# SCH_5G23-dev1_2022-10-18.net
KiCad netlist of a schematic drawn in EasyEDA
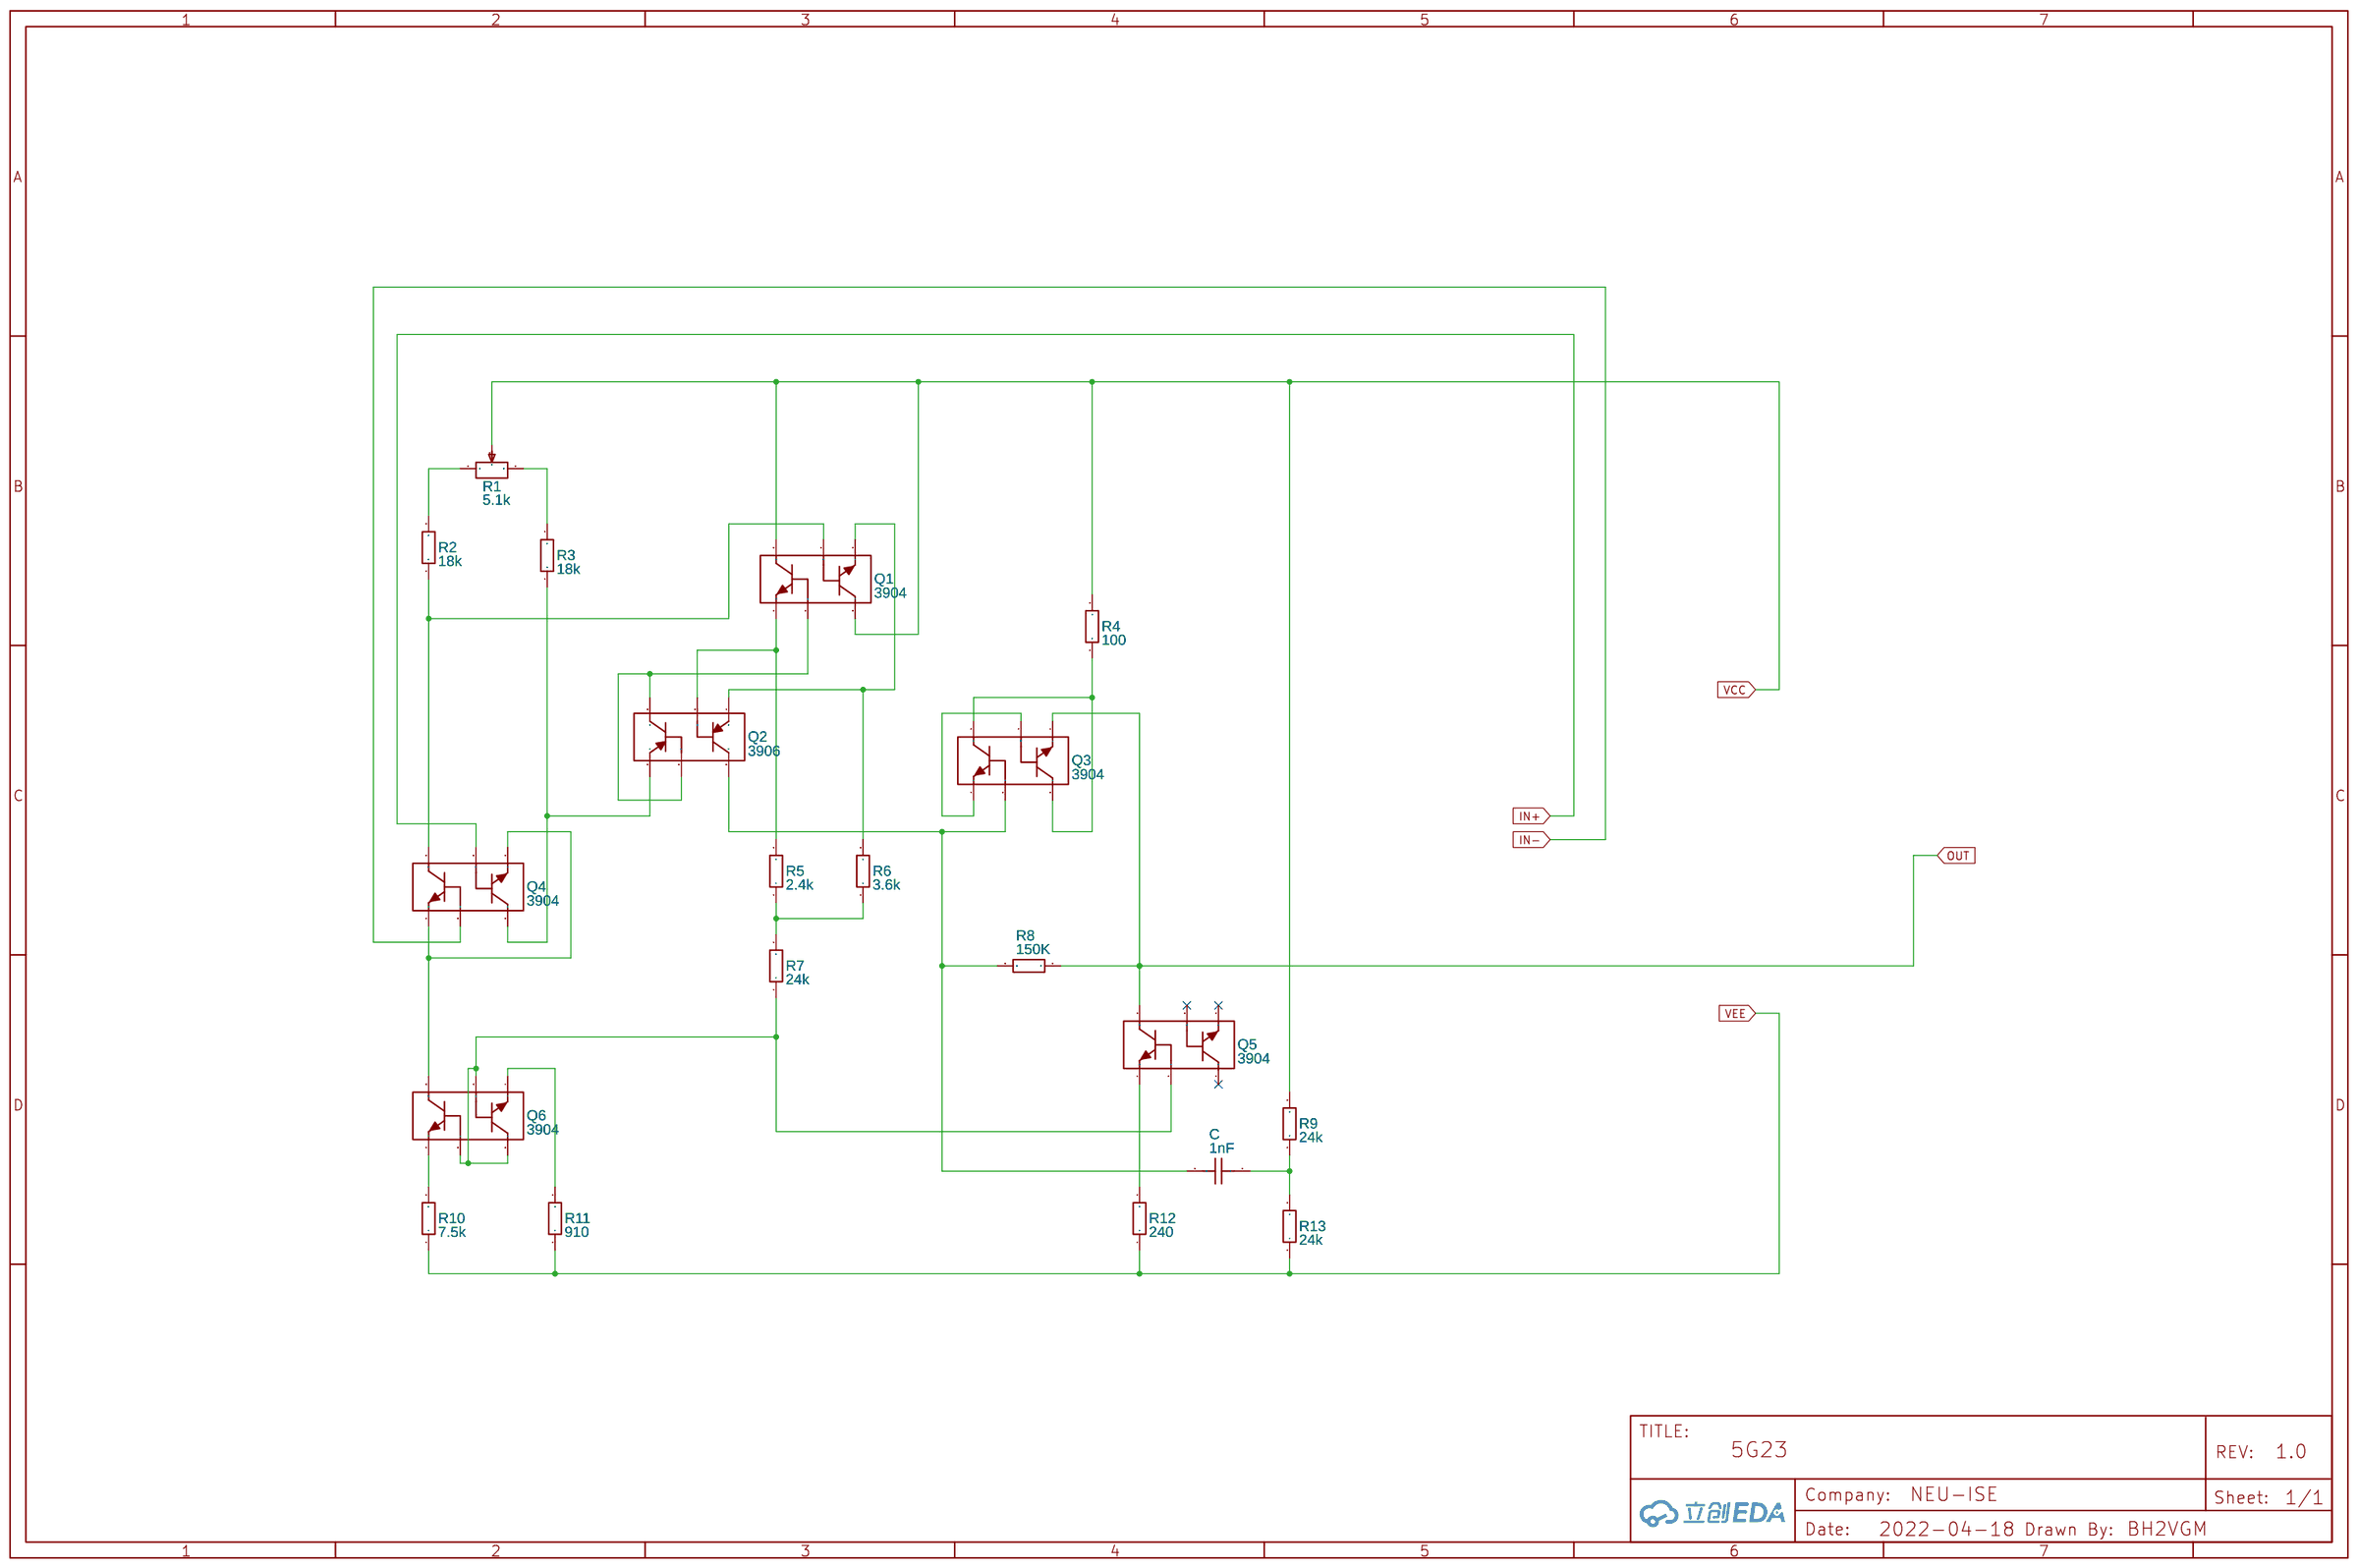
[diagram p0: 5G23]
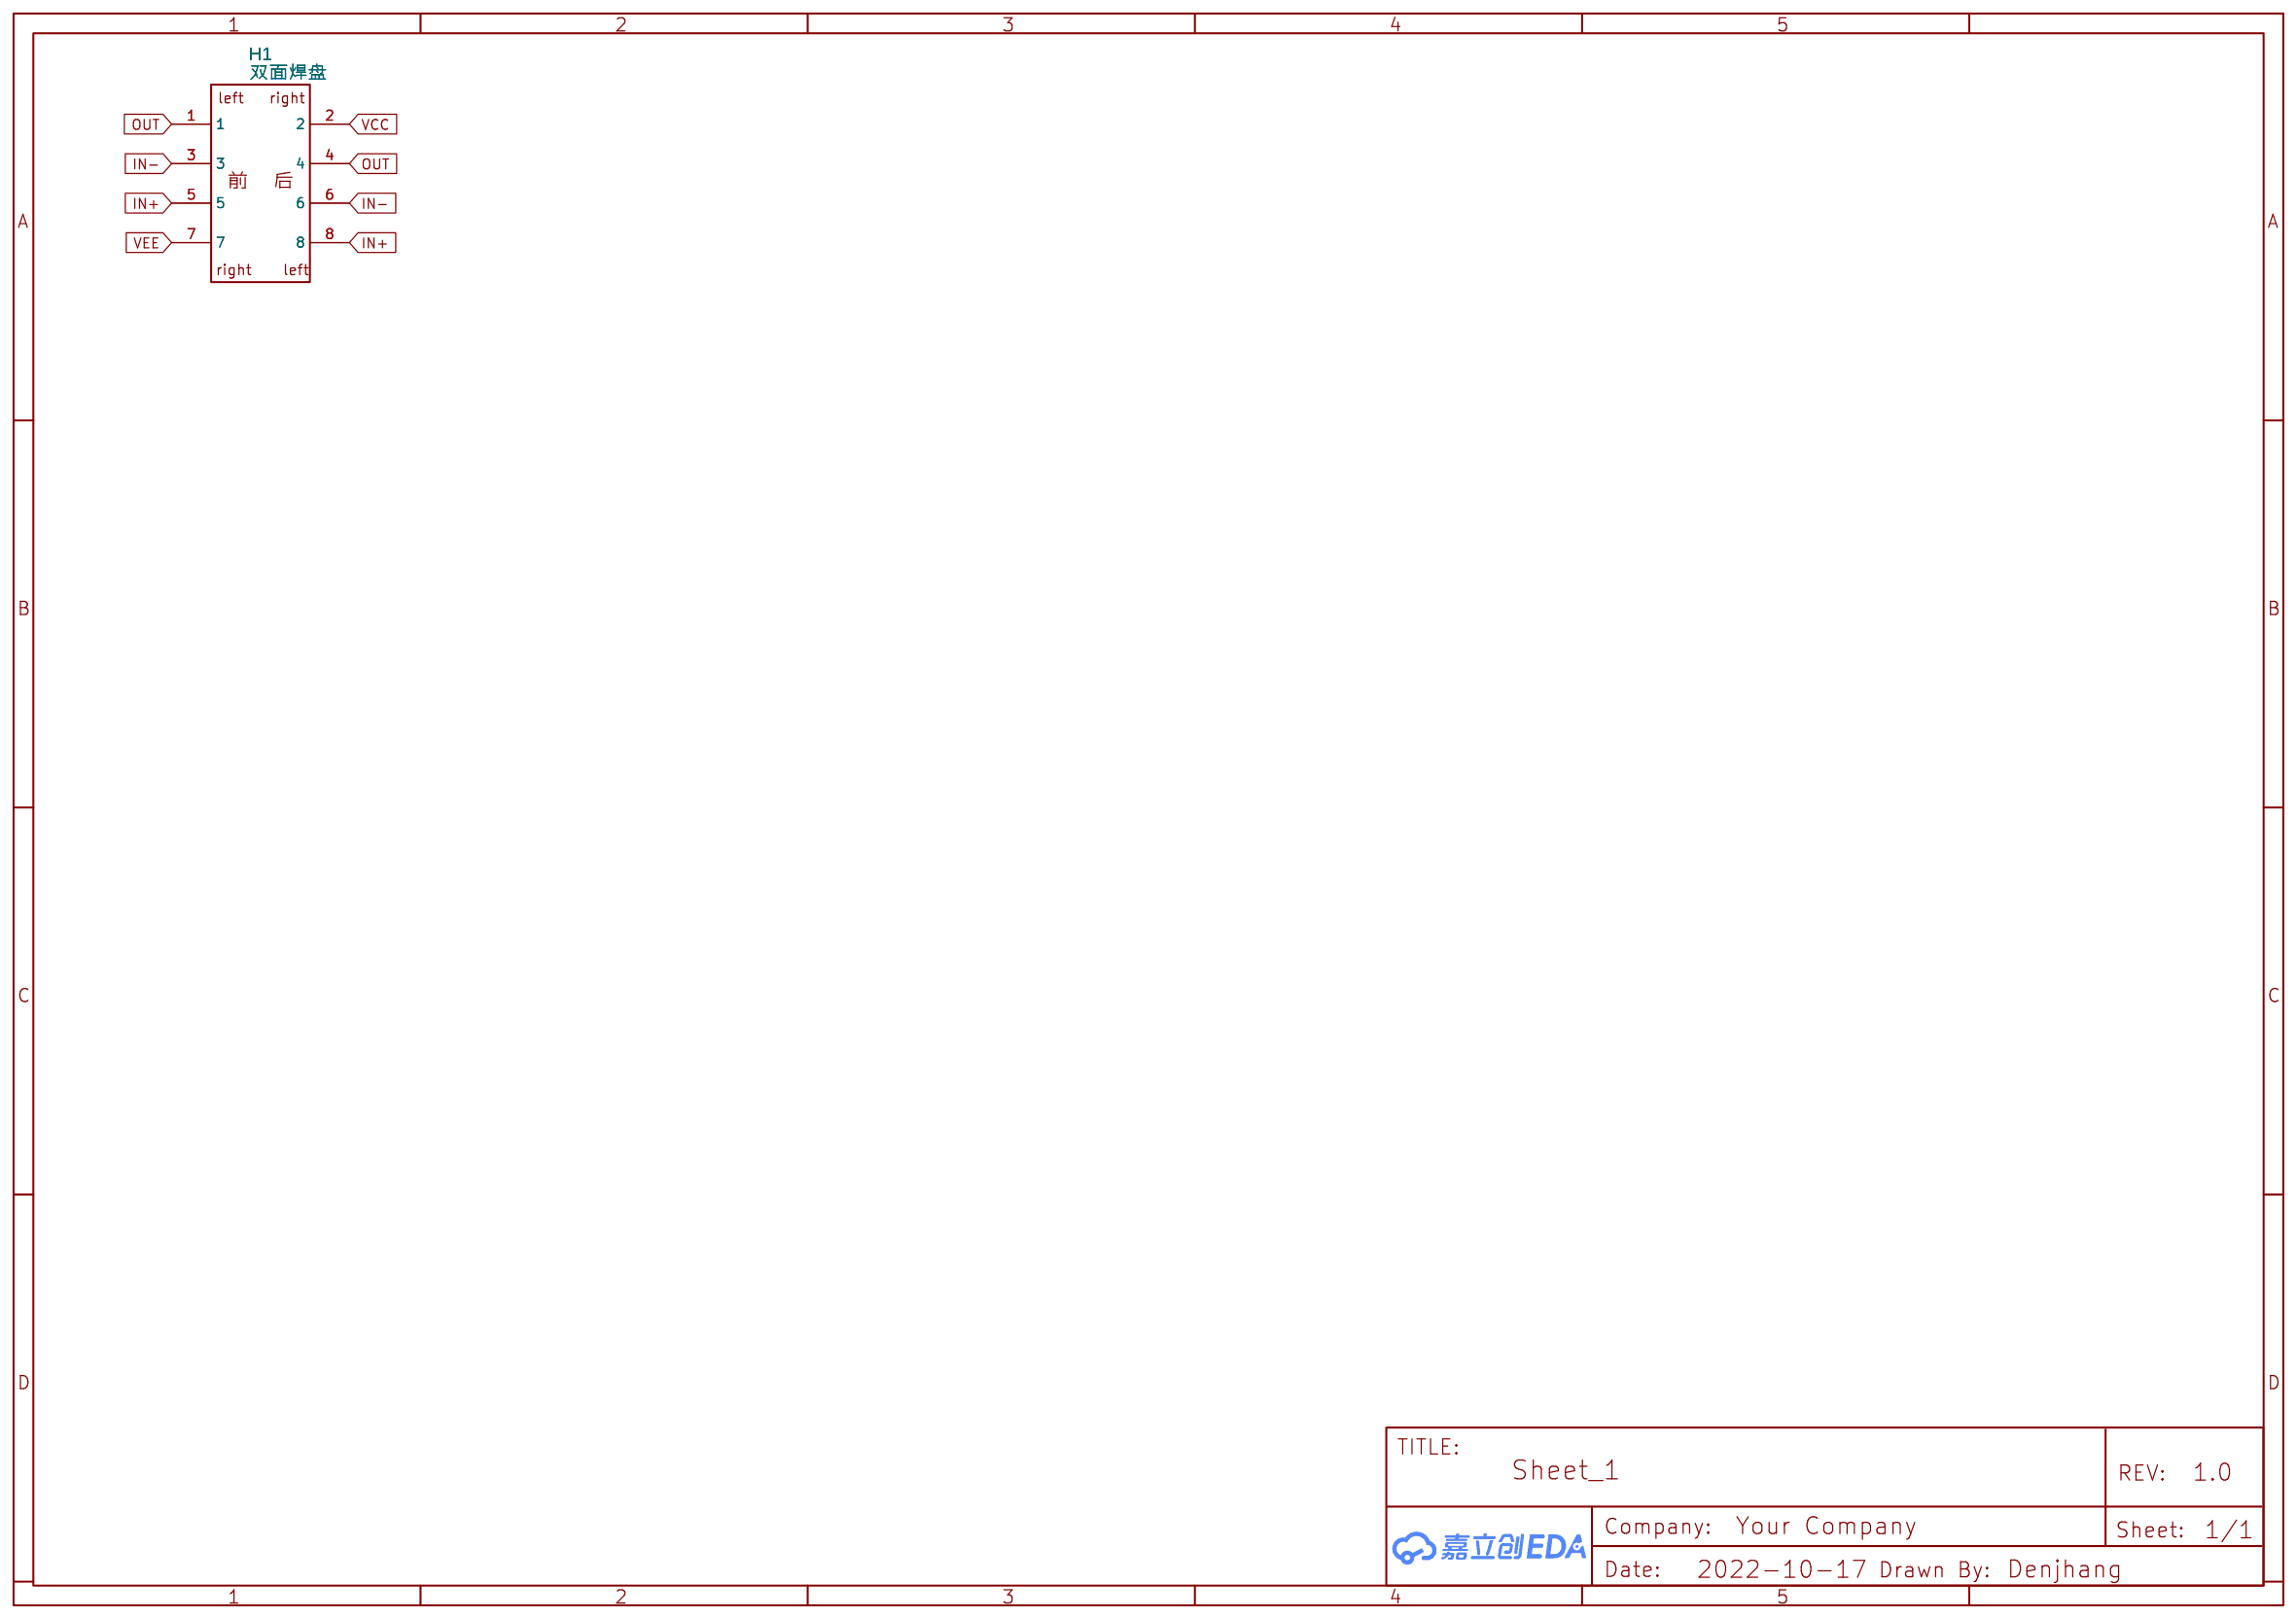
[diagram p1: CONN]

(export (version "E")
  (design (tool "Eeschema 10.0.6"))
  (components
    (comp (ref "C")
      (value "1nF")
      (fields
        (field (name "BOM_Manufacturer Part") "1nF-C0603")
        (field (name "BOM_Supplier Part") "C2940049")
      )
      (libsource (lib "") (part "1NF-C0603"))
    )
    (comp (ref "Q1")
      (value "3904")
      (fields
        (field (name "BOM_Manufacturer Part") "MMDT3904-7-F")
        (field (name "BOM_Supplier Part") "C83572")
      )
      (libsource (lib "") (part "MMDT3904"))
    )
    (comp (ref "Q2")
      (value "3906")
      (fields
        (field (name "BOM_Manufacturer Part") "MMDT3906-TP")
        (field (name "BOM_Supplier Part") "C779248")
      )
      (libsource (lib "") (part "MMDT3906"))
    )
    (comp (ref "Q3")
      (value "3904")
      (fields
        (field (name "BOM_Manufacturer Part") "MMDT3904-7-F")
        (field (name "BOM_Supplier Part") "C83572")
      )
      (libsource (lib "") (part "MMDT3904"))
    )
    (comp (ref "Q4")
      (value "3904")
      (fields
        (field (name "BOM_Manufacturer Part") "MMDT3904-7-F")
        (field (name "BOM_Supplier Part") "C83572")
      )
      (libsource (lib "") (part "MMDT3904"))
    )
    (comp (ref "Q5")
      (value "3904")
      (fields
        (field (name "BOM_Manufacturer Part") "MMDT3904-7-F")
        (field (name "BOM_Supplier Part") "C83572")
      )
      (libsource (lib "") (part "MMDT3904"))
    )
    (comp (ref "Q6")
      (value "3904")
      (fields
        (field (name "BOM_Manufacturer Part") "MMDT3904-7-F")
        (field (name "BOM_Supplier Part") "C83572")
      )
      (libsource (lib "") (part "MMDT3904"))
    )
    (comp (ref "R1")
      (value "5.1k")
      (fields
        (field (name "BOM_Manufacturer Part") "VG039NCHXTB204")
        (field (name "BOM_Supplier Part") "C128551")
      )
      (libsource (lib "") (part "VG039NCHXTB204"))
    )
    (comp (ref "R2")
      (value "18k")
      (fields (field (name "BOM_Manufacturer Part") "0805") (field (name "BOM_Supplier Part") "C9900012715"))
      (libsource (lib "") (part "0805_1"))
    )
    (comp (ref "R3")
      (value "18k")
      (fields (field (name "BOM_Manufacturer Part") "0805") (field (name "BOM_Supplier Part") "C9900012715"))
      (libsource (lib "") (part "0805_1"))
    )
    (comp (ref "R4")
      (value "100")
      (fields (field (name "BOM_Manufacturer Part") "0805") (field (name "BOM_Supplier Part") "C9900012715"))
      (libsource (lib "") (part "0805_1"))
    )
    (comp (ref "R5")
      (value "2.4k")
      (fields (field (name "BOM_Manufacturer Part") "0805") (field (name "BOM_Supplier Part") "C9900012715"))
      (libsource (lib "") (part "0805_1"))
    )
    (comp (ref "R6")
      (value "3.6k")
      (fields (field (name "BOM_Manufacturer Part") "0805") (field (name "BOM_Supplier Part") "C9900012715"))
      (libsource (lib "") (part "0805_1"))
    )
    (comp (ref "R7")
      (value "24k")
      (fields (field (name "BOM_Manufacturer Part") "0805") (field (name "BOM_Supplier Part") "C9900012715"))
      (libsource (lib "") (part "0805_1"))
    )
    (comp (ref "R8")
      (value "150K")
      (fields (field (name "BOM_Manufacturer Part") "0805") (field (name "BOM_Supplier Part") "C9900012715"))
      (libsource (lib "") (part "0805"))
    )
    (comp (ref "R9")
      (value "24k")
      (fields (field (name "BOM_Manufacturer Part") "0805") (field (name "BOM_Supplier Part") "C9900012715"))
      (libsource (lib "") (part "0805_1"))
    )
    (comp (ref "R10")
      (value "7.5k")
      (fields (field (name "BOM_Manufacturer Part") "0805") (field (name "BOM_Supplier Part") "C9900012715"))
      (libsource (lib "") (part "0805_1"))
    )
    (comp (ref "R11")
      (value "910")
      (fields (field (name "BOM_Manufacturer Part") "0805") (field (name "BOM_Supplier Part") "C9900012715"))
      (libsource (lib "") (part "0805_1"))
    )
    (comp (ref "R12")
      (value "240")
      (fields (field (name "BOM_Manufacturer Part") "0805") (field (name "BOM_Supplier Part") "C9900012715"))
      (libsource (lib "") (part "0805_1"))
    )
    (comp (ref "R13")
      (value "24k")
      (fields (field (name "BOM_Manufacturer Part") "0805") (field (name "BOM_Supplier Part") "C9900012715"))
      (libsource (lib "") (part "0805_1"))
    )
    (comp (ref "H1") (value "双面焊盘") (libsource (lib "") (part "双面焊盘")))
  )
  (nets
    (net (code "1") (name "IN+") (class "Default")
      (node (ref "H1") (pin "5") (pinfunction "5_5") (pintype "unspecified"))
      (node (ref "H1") (pin "8") (pinfunction "8_8") (pintype "unspecified"))
      (node (ref "Q4") (pin "5") (pinfunction "B_5") (pintype "unspecified"))
    )
    (net (code "2") (name "IN-") (class "Default")
      (node (ref "H1") (pin "3") (pinfunction "3_3") (pintype "unspecified"))
      (node (ref "H1") (pin "6") (pinfunction "6_6") (pintype "unspecified"))
      (node (ref "Q4") (pin "2") (pinfunction "B_2") (pintype "unspecified"))
    )
    (net (code "3") (name "Net-(C-Pad1)") (class "Default")
      (node (ref "C") (pin "1") (pinfunction "1_1") (pintype "unspecified"))
      (node (ref "Q2") (pin "3") (pinfunction "C_3") (pintype "unspecified"))
      (node (ref "Q3") (pin "2") (pinfunction "B_2") (pintype "unspecified"))
      (node (ref "R8") (pin "2") (pinfunction "2_2") (pintype "unspecified"))
    )
    (net (code "4") (name "Net-(C-Pad2)") (class "Default")
      (node (ref "C") (pin "2") (pinfunction "2_2") (pintype "unspecified"))
      (node (ref "R13") (pin "2") (pinfunction "2_2") (pintype "unspecified"))
      (node (ref "R9") (pin "1") (pinfunction "1_1") (pintype "unspecified"))
    )
    (net (code "5") (name "Net-(Q1-B-Pad2)") (class "Default")
      (node (ref "Q1") (pin "2") (pinfunction "B_2") (pintype "unspecified"))
      (node (ref "Q2") (pin "2") (pinfunction "B_2") (pintype "unspecified"))
      (node (ref "Q2") (pin "6") (pinfunction "C_6") (pintype "unspecified"))
    )
    (net (code "6") (name "Net-(Q1-B-Pad5)") (class "Default")
      (node (ref "Q1") (pin "5") (pinfunction "B_5") (pintype "unspecified"))
      (node (ref "Q4") (pin "6") (pinfunction "C_6") (pintype "unspecified"))
      (node (ref "R2") (pin "1") (pinfunction "1_1") (pintype "unspecified"))
    )
    (net (code "7") (name "Net-(Q1-E-Pad1)") (class "Default")
      (node (ref "Q1") (pin "1") (pinfunction "E_1") (pintype "unspecified"))
      (node (ref "Q2") (pin "5") (pinfunction "B_5") (pintype "unspecified"))
      (node (ref "R5") (pin "2") (pinfunction "2_2") (pintype "unspecified"))
    )
    (net (code "8") (name "Net-(Q1-E-Pad4)") (class "Default")
      (node (ref "Q1") (pin "4") (pinfunction "E_4") (pintype "unspecified"))
      (node (ref "Q2") (pin "4") (pinfunction "E_4") (pintype "unspecified"))
      (node (ref "R6") (pin "2") (pinfunction "2_2") (pintype "unspecified"))
    )
    (net (code "9") (name "Net-(Q2-E-Pad1)") (class "Default")
      (node (ref "Q2") (pin "1") (pinfunction "E_1") (pintype "unspecified"))
      (node (ref "Q4") (pin "3") (pinfunction "C_3") (pintype "unspecified"))
      (node (ref "R3") (pin "1") (pinfunction "1_1") (pintype "unspecified"))
    )
    (net (code "10") (name "Net-(Q3-B-Pad5)") (class "Default")
      (node (ref "Q3") (pin "1") (pinfunction "E_1") (pintype "unspecified"))
      (node (ref "Q3") (pin "5") (pinfunction "B_5") (pintype "unspecified"))
    )
    (net (code "11") (name "Net-(Q3-C-Pad3)") (class "Default")
      (node (ref "Q3") (pin "3") (pinfunction "C_3") (pintype "unspecified"))
      (node (ref "Q3") (pin "6") (pinfunction "C_6") (pintype "unspecified"))
      (node (ref "R4") (pin "1") (pinfunction "1_1") (pintype "unspecified"))
    )
    (net (code "12") (name "Net-(Q4-E-Pad1)") (class "Default")
      (node (ref "Q4") (pin "1") (pinfunction "E_1") (pintype "unspecified"))
      (node (ref "Q4") (pin "4") (pinfunction "E_4") (pintype "unspecified"))
      (node (ref "Q6") (pin "6") (pinfunction "C_6") (pintype "unspecified"))
    )
    (net (code "13") (name "Net-(Q5-B-Pad2)") (class "Default")
      (node (ref "Q5") (pin "2") (pinfunction "B_2") (pintype "unspecified"))
      (node (ref "Q6") (pin "2") (pinfunction "B_2") (pintype "unspecified"))
      (node (ref "Q6") (pin "3") (pinfunction "C_3") (pintype "unspecified"))
      (node (ref "Q6") (pin "5") (pinfunction "B_5") (pintype "unspecified"))
      (node (ref "R7") (pin "1") (pinfunction "1_1") (pintype "unspecified"))
    )
    (net (code "14") (name "Net-(Q5-E-Pad1)") (class "Default")
      (node (ref "Q5") (pin "1") (pinfunction "E_1") (pintype "unspecified"))
      (node (ref "R12") (pin "2") (pinfunction "2_2") (pintype "unspecified"))
    )
    (net (code "15") (name "Net-(Q6-E-Pad1)") (class "Default")
      (node (ref "Q6") (pin "1") (pinfunction "E_1") (pintype "unspecified"))
      (node (ref "R10") (pin "2") (pinfunction "2_2") (pintype "unspecified"))
    )
    (net (code "16") (name "Net-(Q6-E-Pad4)") (class "Default")
      (node (ref "Q6") (pin "4") (pinfunction "E_4") (pintype "unspecified"))
      (node (ref "R11") (pin "2") (pinfunction "2_2") (pintype "unspecified"))
    )
    (net (code "17") (name "Net-(R1-Pad1)") (class "Default")
      (node (ref "R1") (pin "1") (pinfunction "1_1") (pintype "input"))
      (node (ref "R2") (pin "2") (pinfunction "2_2") (pintype "unspecified"))
    )
    (net (code "18") (name "Net-(R1-Pad3)") (class "Default")
      (node (ref "R1") (pin "3") (pinfunction "3_3") (pintype "input"))
      (node (ref "R3") (pin "2") (pinfunction "2_2") (pintype "unspecified"))
    )
    (net (code "19") (name "Net-(R5-Pad1)") (class "Default")
      (node (ref "R5") (pin "1") (pinfunction "1_1") (pintype "unspecified"))
      (node (ref "R6") (pin "1") (pinfunction "1_1") (pintype "unspecified"))
      (node (ref "R7") (pin "2") (pinfunction "2_2") (pintype "unspecified"))
    )
    (net (code "20") (name "OUT") (class "Default")
      (node (ref "H1") (pin "1") (pinfunction "1_1") (pintype "unspecified"))
      (node (ref "H1") (pin "4") (pinfunction "4_4") (pintype "unspecified"))
      (node (ref "Q3") (pin "4") (pinfunction "E_4") (pintype "unspecified"))
      (node (ref "Q5") (pin "6") (pinfunction "C_6") (pintype "unspecified"))
      (node (ref "R8") (pin "1") (pinfunction "1_1") (pintype "unspecified"))
    )
    (net (code "21") (name "VCC") (class "Default")
      (node (ref "H1") (pin "2") (pinfunction "2_2") (pintype "unspecified"))
      (node (ref "Q1") (pin "3") (pinfunction "C_3") (pintype "unspecified"))
      (node (ref "Q1") (pin "6") (pinfunction "C_6") (pintype "unspecified"))
      (node (ref "R1") (pin "2") (pinfunction "2_2") (pintype "input"))
      (node (ref "R4") (pin "2") (pinfunction "2_2") (pintype "unspecified"))
      (node (ref "R9") (pin "2") (pinfunction "2_2") (pintype "unspecified"))
    )
    (net (code "22") (name "VEE") (class "Default")
      (node (ref "H1") (pin "7") (pinfunction "7_7") (pintype "unspecified"))
      (node (ref "R10") (pin "1") (pinfunction "1_1") (pintype "unspecified"))
      (node (ref "R11") (pin "1") (pinfunction "1_1") (pintype "unspecified"))
      (node (ref "R12") (pin "1") (pinfunction "1_1") (pintype "unspecified"))
      (node (ref "R13") (pin "1") (pinfunction "1_1") (pintype "unspecified"))
    )
    (net (code "23") (name "unconnected-(Q5-B-Pad5)") (class "Default")
      (node (ref "Q5") (pin "5") (pinfunction "B_5") (pintype "unspecified+no_connect"))
    )
    (net (code "24") (name "unconnected-(Q5-C-Pad3)") (class "Default")
      (node (ref "Q5") (pin "3") (pinfunction "C_3") (pintype "unspecified+no_connect"))
    )
    (net (code "25") (name "unconnected-(Q5-E-Pad4)") (class "Default")
      (node (ref "Q5") (pin "4") (pinfunction "E_4") (pintype "unspecified+no_connect"))
    )
  )
)
